# E-0056_STM32.net
KiCad netlist of a schematic drawn in Altium Designer
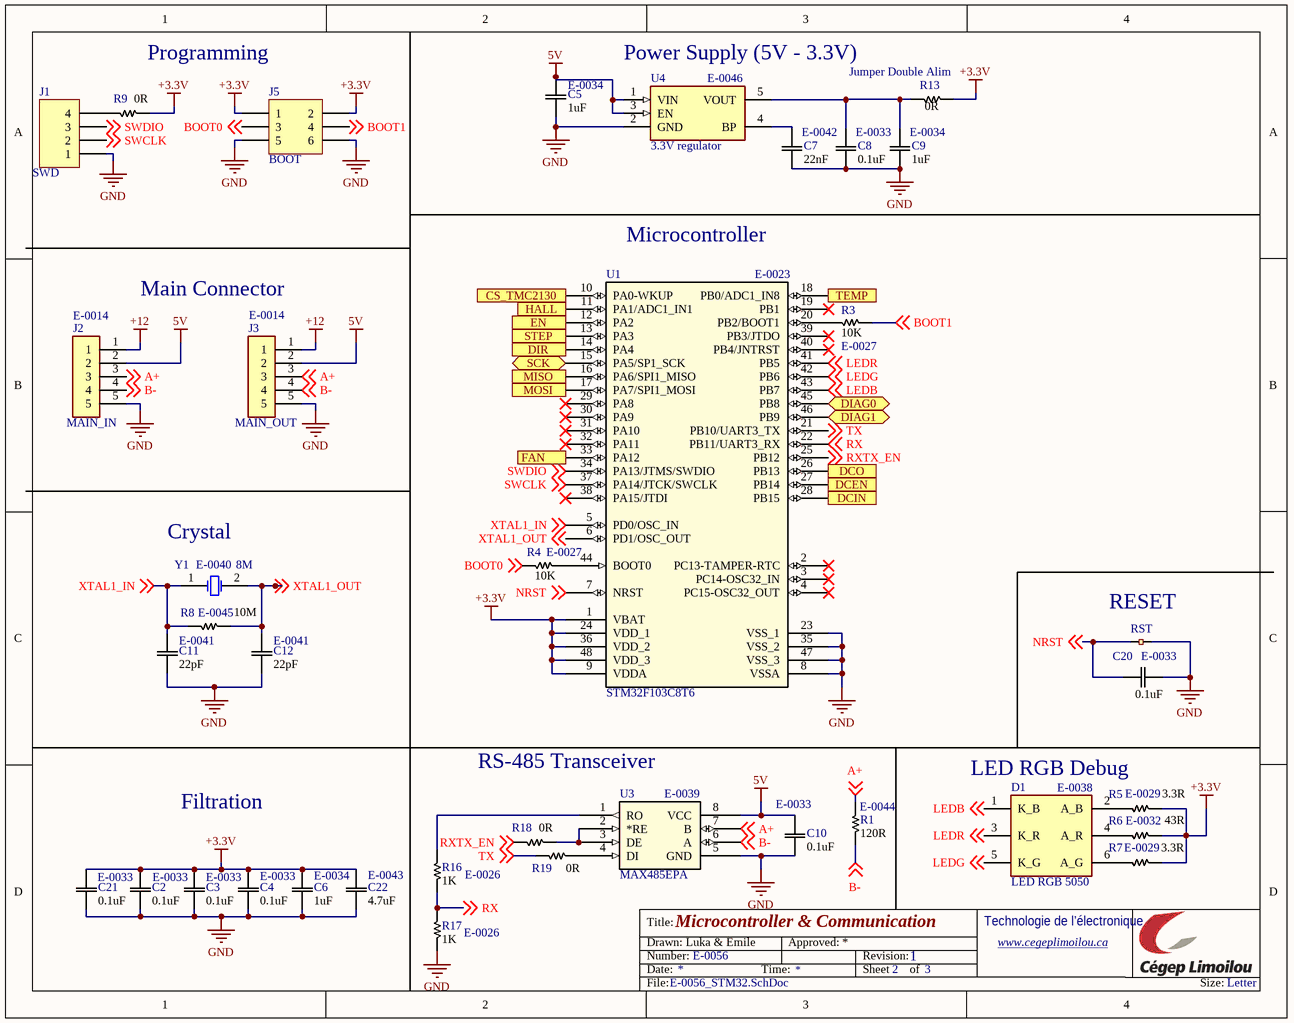
[diagram p0: E-0056_STM32.SchDoc]

(export (version "E")
  (design (tool "Eeschema 10.0.6"))
  (components
    (comp (ref "C2")
      (value "0.1uF")
      (footprint "0603")
      (description "0.1uF Capacitor 0603 SMD")
      (fields
        (field (name "MANUFACTURER_PART_NUMBER") "C0603C104Z3VACTU")
        (field (name "EXCEL NUMBER") "E-0033")
        (field (name "Comment") "E-0033")
        (field (name "COPYRIGHT") "Luka & Émile")
      )
      (libsource (lib "Motor Driver") (part "E-0033"))
    )
    (comp (ref "C3")
      (value "0.1uF")
      (footprint "0603")
      (description "0.1uF Capacitor 0603 SMD")
      (fields
        (field (name "MANUFACTURER_PART_NUMBER") "C0603C104Z3VACTU")
        (field (name "EXCEL NUMBER") "E-0033")
        (field (name "Comment") "E-0033")
        (field (name "COPYRIGHT") "Luka & Émile")
      )
      (libsource (lib "Motor Driver") (part "E-0033"))
    )
    (comp (ref "C4")
      (value "0.1uF")
      (footprint "0603")
      (description "0.1uF Capacitor 0603 SMD")
      (fields
        (field (name "MANUFACTURER_PART_NUMBER") "C0603C104Z3VACTU")
        (field (name "EXCEL NUMBER") "E-0033")
        (field (name "Comment") "E-0033")
        (field (name "COPYRIGHT") "Luka & Émile")
      )
      (libsource (lib "Motor Driver") (part "E-0033"))
    )
    (comp (ref "C5")
      (value "1uF")
      (footprint "0603")
      (description "1uf Capacitor 0603 SMD")
      (fields
        (field (name "MANUFACTURER_PART_NUMBER") "CL10A105KA8NNNC")
        (field (name "EXCEL NUMBER") "E-0034")
        (field (name "Comment") "E-0034")
        (field (name "COPYRIGHT") "Luka & Émile")
      )
      (libsource (lib "Motor Driver") (part "E-0034"))
    )
    (comp (ref "C6")
      (value "1uF")
      (footprint "0603")
      (description "1uf Capacitor 0603 SMD")
      (fields
        (field (name "MANUFACTURER_PART_NUMBER") "CL10A105KA8NNNC")
        (field (name "EXCEL NUMBER") "E-0034")
        (field (name "Comment") "E-0034")
        (field (name "COPYRIGHT") "Luka & Émile")
      )
      (libsource (lib "Motor Driver") (part "E-0034"))
    )
    (comp (ref "C7")
      (value "22nF")
      (footprint "0603")
      (description "22nF Capacitor 0603 SMD")
      (fields
        (field (name "MANUFACTURER_PART_NUMBER") "C0603C223K1RACTU")
        (field (name "EXCEL NUMBER") "E-0042")
        (field (name "Comment") "E-0042")
        (field (name "COPYRIGHT") "Luka & Émile")
      )
      (libsource (lib "Motor Driver") (part "E-0042"))
    )
    (comp (ref "C8")
      (value "0.1uF")
      (footprint "0603")
      (description "0.1uF Capacitor 0603 SMD")
      (fields
        (field (name "MANUFACTURER_PART_NUMBER") "C0603C104Z3VACTU")
        (field (name "EXCEL NUMBER") "E-0033")
        (field (name "Comment") "E-0033")
        (field (name "COPYRIGHT") "Luka & Émile")
      )
      (libsource (lib "Motor Driver") (part "E-0033"))
    )
    (comp (ref "C9")
      (value "1uF")
      (footprint "0603")
      (description "1uf Capacitor 0603 SMD")
      (fields
        (field (name "MANUFACTURER_PART_NUMBER") "CL10A105KA8NNNC")
        (field (name "EXCEL NUMBER") "E-0034")
        (field (name "Comment") "E-0034")
        (field (name "COPYRIGHT") "Luka & Émile")
      )
      (libsource (lib "Motor Driver") (part "E-0034"))
    )
    (comp (ref "C10")
      (value "0.1uF")
      (footprint "0603")
      (description "0.1uF Capacitor 0603 SMD")
      (fields
        (field (name "MANUFACTURER_PART_NUMBER") "C0603C104Z3VACTU")
        (field (name "EXCEL NUMBER") "E-0033")
        (field (name "Comment") "E-0033")
        (field (name "COPYRIGHT") "Luka & Émile")
      )
      (libsource (lib "Motor Driver") (part "E-0033"))
    )
    (comp (ref "C11")
      (value "22pF")
      (footprint "0603")
      (description "22pF Capacitor 0603 SMD")
      (fields
        (field (name "MANUFACTURER_PART_NUMBER") "C0603C220J1GACTU")
        (field (name "EXCEL NUMBER") "E-0041")
        (field (name "Comment") "E-0041")
        (field (name "COPYRIGHT") "Luka & Émile")
      )
      (libsource (lib "Motor Driver") (part "E-0041"))
    )
    (comp (ref "C12")
      (value "22pF")
      (footprint "0603")
      (description "22pF Capacitor 0603 SMD")
      (fields
        (field (name "MANUFACTURER_PART_NUMBER") "C0603C220J1GACTU")
        (field (name "EXCEL NUMBER") "E-0041")
        (field (name "Comment") "E-0041")
        (field (name "COPYRIGHT") "Luka & Émile")
      )
      (libsource (lib "Motor Driver") (part "E-0041"))
    )
    (comp (ref "C20")
      (value "0.1uF")
      (footprint "0603")
      (description "0.1uF Capacitor 0603 SMD")
      (fields
        (field (name "MANUFACTURER_PART_NUMBER") "C0603C104Z3VACTU")
        (field (name "EXCEL NUMBER") "E-0033")
        (field (name "Comment") "E-0033")
        (field (name "COPYRIGHT") "Luka & Émile")
      )
      (libsource (lib "Motor Driver") (part "E-0033"))
    )
    (comp (ref "C21")
      (value "0.1uF")
      (footprint "0603")
      (description "0.1uF Capacitor 0603 SMD")
      (fields
        (field (name "MANUFACTURER_PART_NUMBER") "C0603C104Z3VACTU")
        (field (name "EXCEL NUMBER") "E-0033")
        (field (name "Comment") "E-0033")
        (field (name "COPYRIGHT") "Luka & Émile")
      )
      (libsource (lib "Motor Driver") (part "E-0033"))
    )
    (comp (ref "C22")
      (value "4.7uF")
      (footprint "0603")
      (description "4.7uF Capacitor 0603 SMD")
      (fields
        (field (name "MANUFACTURER_PART_NUMBER") "C0603C475K9PACTU")
        (field (name "EXCEL NUMBER") "E-0043")
        (field (name "Comment") "E-0043")
        (field (name "COPYRIGHT") "Luka & Émile")
      )
      (libsource (lib "Motor Driver") (part "E-0043"))
    )
    (comp (ref "D1")
      (value "LED RGB 5050")
      (footprint "LED 5050")
      (fields
        (field (name "MANUFACTURER_PART_NUMBER") "150505M173300")
        (field (name "EXCEL NUMBER") "E-0038")
        (field (name "COPYRIGHT") "Luka & Émile")
      )
      (libsource (lib "Motor Driver") (part "E-0038"))
    )
    (comp (ref "J1")
      (value "SWD")
      (footprint "HDR1X4")
      (description "Header, 4POS")
      (fields
        (field (name "MANUFACTURER_PART_NUMBER") "61300411121")
        (field (name "COPYRIGHT") "Luka & Émile")
      )
      (libsource (lib "Motor Driver") (part "E-0048"))
    )
    (comp (ref "J2")
      (value "MAIN_IN")
      (footprint "JST 5POS 2.5mm 90°")
      (description "Connector JST 5POS")
      (fields
        (field (name "MANUFACTURER_PART_NUMBER") "S5B-XH-A-1(LF)(SN)")
        (field (name "EXCEL NUMBER") "E-0014")
        (field (name "COPYRIGHT") "Luka & Émile")
      )
      (libsource (lib "Motor Driver") (part "E-0014"))
    )
    (comp (ref "J3")
      (value "MAIN_OUT")
      (footprint "JST 5POS 2.5mm 90°")
      (description "Connector JST 5POS")
      (fields
        (field (name "MANUFACTURER_PART_NUMBER") "S5B-XH-A-1(LF)(SN)")
        (field (name "EXCEL NUMBER") "E-0014")
        (field (name "COPYRIGHT") "Luka & Émile")
      )
      (libsource (lib "Motor Driver") (part "E-0014"))
    )
    (comp (ref "J5")
      (value "BOOT")
      (footprint "Header 3x2 1.27mm SMD")
      (description "Header, 3-Pin, Dual row")
      (fields
        (field (name "MANUFACTURER_PART_NUMBER") "GRPB032VWVN-RC")
        (field (name "COPYRIGHT") "Luka & Émile")
      )
      (libsource (lib "Motor Driver") (part "E-0049"))
    )
    (comp (ref "R1")
      (value "120R")
      (footprint "0603")
      (description "120R Resistor 0603 SMD")
      (fields
        (field (name "MANUFACTURER_PART_NUMBER") "KDV06FR120ET")
        (field (name "EXCEL NUMBER") "E-0044")
        (field (name "Comment") "E-0044")
        (field (name "COPYRIGHT") "Luka & Émile")
      )
      (libsource (lib "Motor Driver") (part "E-0044"))
    )
    (comp (ref "R3")
      (value "10K")
      (footprint "0603")
      (description "10K Resistor 0603 SMD")
      (fields
        (field (name "MANUFACTURER_PART_NUMBER") "RMCF0603JT10K0")
        (field (name "EXCEL NUMBER") "E-0027")
        (field (name "Comment") "Resistor 0603")
        (field (name "COPYRIGHT") "Luka & Émile")
      )
      (libsource (lib "Motor Driver") (part "E-0027"))
    )
    (comp (ref "R4")
      (value "10K")
      (footprint "0603")
      (description "10K Resistor 0603 SMD")
      (fields
        (field (name "MANUFACTURER_PART_NUMBER") "RMCF0603JT10K0")
        (field (name "EXCEL NUMBER") "E-0027")
        (field (name "Comment") "Resistor 0603")
        (field (name "COPYRIGHT") "Luka & Émile")
      )
      (libsource (lib "Motor Driver") (part "E-0027"))
    )
    (comp (ref "R5")
      (value "3.3R")
      (footprint "0603")
      (description "3.3R Resistor 0603 SMD")
      (fields
        (field (name "MANUFACTURER_PART_NUMBER") "MCR03ERTJ3R3")
        (field (name "EXCEL NUMBER") "E-0029")
        (field (name "Comment") "E-0029")
        (field (name "COPYRIGHT") "Luka & Émile")
      )
      (libsource (lib "Motor Driver") (part "E-0029"))
    )
    (comp (ref "R6")
      (value "43R")
      (footprint "0603")
      (description "43R Resistor 0603 SMD")
      (fields
        (field (name "MANUFACTURER_PART_NUMBER") "RK73B1JTTD430J")
        (field (name "EXCEL NUMBER") "E-0032")
        (field (name "Comment") "E-0032")
        (field (name "COPYRIGHT") "Luka & Émile")
      )
      (libsource (lib "Motor Driver") (part "E-0032"))
    )
    (comp (ref "R7")
      (value "3.3R")
      (footprint "0603")
      (description "3.3R Resistor 0603 SMD")
      (fields
        (field (name "MANUFACTURER_PART_NUMBER") "MCR03ERTJ3R3")
        (field (name "EXCEL NUMBER") "E-0029")
        (field (name "Comment") "E-0029")
        (field (name "COPYRIGHT") "Luka & Émile")
      )
      (libsource (lib "Motor Driver") (part "E-0029"))
    )
    (comp (ref "R8")
      (value "10M")
      (footprint "0603")
      (description "10M Resistor 0603 SMD")
      (fields
        (field (name "MANUFACTURER_PART_NUMBER") "CRCW060310M0FKEAC")
        (field (name "EXCEL NUMBER") "E-0045")
        (field (name "Comment") "E-0045")
        (field (name "COPYRIGHT") "Luka & Émile")
      )
      (libsource (lib "Motor Driver") (part "E-0045"))
    )
    (comp (ref "R9")
      (value "0R")
      (footprint "0603")
      (description "Jumper 0603")
      (fields (field (name "Comment") "Jumper") (field (name "COPYRIGHT") "Luka & Émile"))
      (libsource (lib "Motor Driver") (part "Jumper"))
    )
    (comp (ref "R13")
      (value "0R")
      (footprint "0603")
      (description "Jumper 0603")
      (fields (field (name "Comment") "Jumper") (field (name "COPYRIGHT") "Luka & Émile"))
      (libsource (lib "Motor Driver") (part "Jumper"))
    )
    (comp (ref "R16")
      (value "1K")
      (footprint "0603")
      (description "1K Resistor 0603 SMD")
      (fields
        (field (name "MANUFACTURER_PART_NUMBER") "RK73B1JTTD102J")
        (field (name "EXCEL NUMBER") "E-0026")
        (field (name "Comment") "E-0026")
        (field (name "COPYRIGHT") "Luka & Émile")
      )
      (libsource (lib "Motor Driver") (part "E-0026"))
    )
    (comp (ref "R17")
      (value "1K")
      (footprint "0603")
      (description "1K Resistor 0603 SMD")
      (fields
        (field (name "MANUFACTURER_PART_NUMBER") "RK73B1JTTD102J")
        (field (name "EXCEL NUMBER") "E-0026")
        (field (name "Comment") "E-0026")
        (field (name "COPYRIGHT") "Luka & Émile")
      )
      (libsource (lib "Motor Driver") (part "E-0026"))
    )
    (comp (ref "R18")
      (value "0R")
      (footprint "0603")
      (description "Jumper 0603")
      (fields (field (name "Comment") "Jumper") (field (name "COPYRIGHT") "Luka & Émile"))
      (libsource (lib "Motor Driver") (part "Jumper"))
    )
    (comp (ref "R19")
      (value "0R")
      (footprint "0603")
      (description "Jumper 0603")
      (fields (field (name "Comment") "Jumper") (field (name "COPYRIGHT") "Luka & Émile"))
      (libsource (lib "Motor Driver") (part "Jumper"))
    )
    (comp (ref "RST")
      (value "~")
      (footprint "PAD")
      (description "SMD Pad for contact")
      (fields (field (name "COPYRIGHT") "Luka & Émile"))
      (libsource (lib "Motor Driver") (part "PAD"))
    )
    (comp (ref "U1")
      (value "STM32F103C8T6")
      (footprint "LQFP-48")
      (description "STM32F103C8T6 Bluepill")
      (fields
        (field (name "MANUFACTURER_PART_NUMBER") "STM32F103C8T6TR")
        (field (name "EXCEL NUMBER") "E-0023")
        (field (name "COPYRIGHT") "Luka & Émile")
      )
      (libsource (lib "Motor Driver") (part "E-0023"))
    )
    (comp (ref "U3")
      (value "MAX485EPA")
      (footprint "DIP 8 - 3D")
      (description "RS485 Communication")
      (fields
        (field (name "MANUFACTURER_PART_NUMBER") "MAX485CPA+")
        (field (name "EXCEL NUMBER") "E-0039")
        (field (name "COPYRIGHT") "Luka & Émile")
      )
      (libsource (lib "Motor Driver") (part "E-0039"))
    )
    (comp (ref "U4")
      (value "3.3V regulator")
      (footprint "SamacSys:SOT94P279X130-5N")
      (description "Voltage Regulator 3.3V SOT-23-5")
      (fields
        (field (name "MANUFACTURER_PART_NUMBER") "RT9193-28GB")
        (field (name "EXCEL NUMBER") "E-0046")
        (field (name "COPYRIGHT") "Luka & Émile")
      )
      (libsource (lib "Motor Driver") (part "E-0046"))
    )
    (comp (ref "Y1")
      (value "8M")
      (footprint "ATS080B-E")
      (description "Crystal 8M")
      (fields
        (field (name "MANUFACTURER_PART_NUMBER") "ATS080B-E")
        (field (name "EXCEL NUMBER") "E-0040")
        (field (name "COPYRIGHT") "Luka & Émile")
      )
      (libsource (lib "Motor Driver") (part "E-0040"))
    )
  )
  (nets
    (net (code "1") (name "+3.3V") (class "Default")
      (node (ref "C2") (pin "2") (pinfunction "2_2") (pintype "passive"))
      (node (ref "C21") (pin "2") (pinfunction "2_2") (pintype "passive"))
      (node (ref "C22") (pin "2") (pinfunction "2_2") (pintype "passive"))
      (node (ref "C3") (pin "2") (pinfunction "2_2") (pintype "passive"))
      (node (ref "C4") (pin "2") (pinfunction "2_2") (pintype "passive"))
      (node (ref "C6") (pin "2") (pinfunction "2_2") (pintype "passive"))
      (node (ref "J5") (pin "1") (pinfunction "1_1") (pintype "passive"))
      (node (ref "J5") (pin "2") (pinfunction "2_2") (pintype "passive"))
      (node (ref "R13") (pin "2") (pinfunction "2_2") (pintype "passive"))
      (node (ref "R5") (pin "2") (pinfunction "2_2") (pintype "passive"))
      (node (ref "R6") (pin "2") (pinfunction "2_2") (pintype "passive"))
      (node (ref "R7") (pin "2") (pinfunction "2_2") (pintype "passive"))
      (node (ref "R9") (pin "2") (pinfunction "2_2") (pintype "passive"))
      (node (ref "U1") (pin "1") (pinfunction "VBAT_1") (pintype "power_in"))
      (node (ref "U1") (pin "24") (pinfunction "VDD_1_24") (pintype "power_in"))
      (node (ref "U1") (pin "36") (pinfunction "VDD_2_36") (pintype "power_in"))
      (node (ref "U1") (pin "48") (pinfunction "VDD_3_48") (pintype "power_in"))
      (node (ref "U1") (pin "9") (pinfunction "VDDA_9") (pintype "power_in"))
    )
    (net (code "2") (name "+12") (class "Default")
      (node (ref "J2") (pin "1") (pinfunction "1_1") (pintype "passive"))
      (node (ref "J3") (pin "1") (pinfunction "1_1") (pintype "passive"))
    )
    (net (code "3") (name "/CS_TMC2130") (class "Default")
      (node (ref "U1") (pin "10") (pinfunction "PA0-WKUP_10") (pintype "bidirectional"))
    )
    (net (code "4") (name "/DCEN") (class "Default")
      (node (ref "U1") (pin "27") (pinfunction "PB14_27") (pintype "bidirectional"))
    )
    (net (code "5") (name "/DCIN") (class "Default")
      (node (ref "U1") (pin "28") (pinfunction "PB15_28") (pintype "bidirectional"))
    )
    (net (code "6") (name "/DCO") (class "Default")
      (node (ref "U1") (pin "26") (pinfunction "PB13_26") (pintype "bidirectional"))
    )
    (net (code "7") (name "/DIAG0") (class "Default")
      (node (ref "U1") (pin "45") (pinfunction "PB8_45") (pintype "bidirectional"))
    )
    (net (code "8") (name "/DIAG1") (class "Default")
      (node (ref "U1") (pin "46") (pinfunction "PB9_46") (pintype "bidirectional"))
    )
    (net (code "9") (name "/DIR") (class "Default")
      (node (ref "U1") (pin "14") (pinfunction "PA4_14") (pintype "bidirectional"))
    )
    (net (code "10") (name "/EN") (class "Default")
      (node (ref "U1") (pin "12") (pinfunction "PA2_12") (pintype "bidirectional"))
    )
    (net (code "11") (name "/FAN") (class "Default")
      (node (ref "U1") (pin "33") (pinfunction "PA12_33") (pintype "bidirectional"))
    )
    (net (code "12") (name "/HALL") (class "Default")
      (node (ref "U1") (pin "11") (pinfunction "PA1/ADC1_IN1_11") (pintype "bidirectional"))
    )
    (net (code "13") (name "/MISO") (class "Default")
      (node (ref "U1") (pin "16") (pinfunction "PA6/SPI1_MISO_16") (pintype "bidirectional"))
    )
    (net (code "14") (name "/MOSI") (class "Default")
      (node (ref "U1") (pin "17") (pinfunction "PA7/SPI1_MOSI_17") (pintype "bidirectional"))
    )
    (net (code "15") (name "/SCK") (class "Default")
      (node (ref "U1") (pin "15") (pinfunction "PA5/SP1_SCK_15") (pintype "bidirectional"))
    )
    (net (code "16") (name "/STEP") (class "Default")
      (node (ref "U1") (pin "13") (pinfunction "PA3_13") (pintype "bidirectional"))
    )
    (net (code "17") (name "/TEMP") (class "Default")
      (node (ref "U1") (pin "18") (pinfunction "PB0/ADC1_IN8_18") (pintype "bidirectional"))
    )
    (net (code "18") (name "5V") (class "Default")
      (node (ref "C10") (pin "2") (pinfunction "2_2") (pintype "passive"))
      (node (ref "C5") (pin "2") (pinfunction "2_2") (pintype "passive"))
      (node (ref "J2") (pin "2") (pinfunction "2_2") (pintype "passive"))
      (node (ref "J3") (pin "2") (pinfunction "2_2") (pintype "passive"))
      (node (ref "U3") (pin "8") (pinfunction "VCC_8") (pintype "power_in"))
      (node (ref "U4") (pin "1") (pinfunction "VIN_1") (pintype "input"))
      (node (ref "U4") (pin "3") (pinfunction "EN_3") (pintype "input"))
    )
    (net (code "19") (name "A+") (class "Default")
      (node (ref "J2") (pin "3") (pinfunction "3_3") (pintype "passive"))
      (node (ref "J3") (pin "3") (pinfunction "3_3") (pintype "passive"))
      (node (ref "R1") (pin "2") (pinfunction "2_2") (pintype "passive"))
      (node (ref "U3") (pin "7") (pinfunction "B_7") (pintype "bidirectional"))
    )
    (net (code "20") (name "B-") (class "Default")
      (node (ref "J2") (pin "4") (pinfunction "4_4") (pintype "passive"))
      (node (ref "J3") (pin "4") (pinfunction "4_4") (pintype "passive"))
      (node (ref "R1") (pin "1") (pinfunction "1_1") (pintype "passive"))
      (node (ref "U3") (pin "6") (pinfunction "A_6") (pintype "bidirectional"))
    )
    (net (code "21") (name "BOOT0") (class "Default")
      (node (ref "J5") (pin "3") (pinfunction "3_3") (pintype "passive"))
      (node (ref "R4") (pin "1") (pinfunction "1_1") (pintype "passive"))
    )
    (net (code "22") (name "BOOT1") (class "Default")
      (node (ref "J5") (pin "4") (pinfunction "4_4") (pintype "passive"))
      (node (ref "R3") (pin "2") (pinfunction "2_2") (pintype "passive"))
    )
    (net (code "23") (name "GND") (class "Default")
      (node (ref "C10") (pin "1") (pinfunction "1_1") (pintype "passive"))
      (node (ref "C11") (pin "1") (pinfunction "1_1") (pintype "passive"))
      (node (ref "C12") (pin "1") (pinfunction "1_1") (pintype "passive"))
      (node (ref "C2") (pin "1") (pinfunction "1_1") (pintype "passive"))
      (node (ref "C20") (pin "1") (pinfunction "1_1") (pintype "passive"))
      (node (ref "C21") (pin "1") (pinfunction "1_1") (pintype "passive"))
      (node (ref "C22") (pin "1") (pinfunction "1_1") (pintype "passive"))
      (node (ref "C3") (pin "1") (pinfunction "1_1") (pintype "passive"))
      (node (ref "C4") (pin "1") (pinfunction "1_1") (pintype "passive"))
      (node (ref "C5") (pin "1") (pinfunction "1_1") (pintype "passive"))
      (node (ref "C6") (pin "1") (pinfunction "1_1") (pintype "passive"))
      (node (ref "C7") (pin "1") (pinfunction "1_1") (pintype "passive"))
      (node (ref "C8") (pin "1") (pinfunction "1_1") (pintype "passive"))
      (node (ref "C9") (pin "1") (pinfunction "1_1") (pintype "passive"))
      (node (ref "J1") (pin "1") (pinfunction "1_1") (pintype "passive"))
      (node (ref "J2") (pin "5") (pinfunction "5_5") (pintype "passive"))
      (node (ref "J3") (pin "5") (pinfunction "5_5") (pintype "passive"))
      (node (ref "J5") (pin "5") (pinfunction "5_5") (pintype "passive"))
      (node (ref "J5") (pin "6") (pinfunction "6_6") (pintype "passive"))
      (node (ref "R17") (pin "2") (pinfunction "2_2") (pintype "passive"))
      (node (ref "RST") (pin "1") (pinfunction "1_1") (pintype "passive"))
      (node (ref "U1") (pin "23") (pinfunction "VSS_1_23") (pintype "power_in"))
      (node (ref "U1") (pin "35") (pinfunction "VSS_2_35") (pintype "power_in"))
      (node (ref "U1") (pin "47") (pinfunction "VSS_3_47") (pintype "power_in"))
      (node (ref "U1") (pin "8") (pinfunction "VSSA_8") (pintype "power_in"))
      (node (ref "U3") (pin "5") (pinfunction "GND_5") (pintype "power_in"))
      (node (ref "U4") (pin "2") (pinfunction "GND_2") (pintype "power_in"))
    )
    (net (code "24") (name "LEDB") (class "Default")
      (node (ref "D1") (pin "1") (pinfunction "K_B_1") (pintype "passive"))
      (node (ref "U1") (pin "43") (pinfunction "PB7_43") (pintype "bidirectional"))
    )
    (net (code "25") (name "LEDG") (class "Default")
      (node (ref "D1") (pin "5") (pinfunction "K_G_5") (pintype "passive"))
      (node (ref "U1") (pin "42") (pinfunction "PB6_42") (pintype "bidirectional"))
    )
    (net (code "26") (name "LEDR") (class "Default")
      (node (ref "D1") (pin "3") (pinfunction "K_R_3") (pintype "passive"))
      (node (ref "U1") (pin "41") (pinfunction "PB5_41") (pintype "bidirectional"))
    )
    (net (code "27") (name "NRST") (class "Default")
      (node (ref "C20") (pin "2") (pinfunction "2_2") (pintype "passive"))
      (node (ref "RST") (pin "2") (pinfunction "2_2") (pintype "passive"))
      (node (ref "U1") (pin "7") (pinfunction "NRST_7") (pintype "bidirectional"))
    )
    (net (code "28") (name "Net-(D1-A_B)") (class "Default")
      (node (ref "D1") (pin "2") (pinfunction "A_B_2") (pintype "passive"))
      (node (ref "R5") (pin "1") (pinfunction "1_1") (pintype "passive"))
    )
    (net (code "29") (name "Net-(D1-A_G)") (class "Default")
      (node (ref "D1") (pin "6") (pinfunction "A_G_6") (pintype "passive"))
      (node (ref "R7") (pin "1") (pinfunction "1_1") (pintype "passive"))
    )
    (net (code "30") (name "Net-(D1-A_R)") (class "Default")
      (node (ref "D1") (pin "4") (pinfunction "A_R_4") (pintype "passive"))
      (node (ref "R6") (pin "1") (pinfunction "1_1") (pintype "passive"))
    )
    (net (code "31") (name "Net-(J1-Pad4)") (class "Default")
      (node (ref "J1") (pin "4") (pinfunction "4_4") (pintype "passive"))
      (node (ref "R9") (pin "1") (pinfunction "1_1") (pintype "passive"))
    )
    (net (code "32") (name "Net-(U1-BOOT0)") (class "Default")
      (node (ref "R4") (pin "2") (pinfunction "2_2") (pintype "passive"))
      (node (ref "U1") (pin "44") (pinfunction "BOOT0_44") (pintype "input"))
    )
    (net (code "33") (name "Net-(U1-PB2{slash}BOOT1)") (class "Default")
      (node (ref "R3") (pin "1") (pinfunction "1_1") (pintype "passive"))
      (node (ref "U1") (pin "20") (pinfunction "PB2/BOOT1_20") (pintype "bidirectional"))
    )
    (net (code "34") (name "Net-(U3-*RE)") (class "Default")
      (node (ref "R18") (pin "2") (pinfunction "2_2") (pintype "passive"))
      (node (ref "U3") (pin "2") (pinfunction "*RE_2") (pintype "input"))
      (node (ref "U3") (pin "3") (pinfunction "DE_3") (pintype "input"))
    )
    (net (code "35") (name "Net-(U3-DI)") (class "Default")
      (node (ref "R19") (pin "2") (pinfunction "2_2") (pintype "passive"))
      (node (ref "U3") (pin "4") (pinfunction "DI_4") (pintype "input"))
    )
    (net (code "36") (name "Net-(U3-RO)") (class "Default")
      (node (ref "R16") (pin "1") (pinfunction "1_1") (pintype "passive"))
      (node (ref "U3") (pin "1") (pinfunction "RO_1") (pintype "output"))
    )
    (net (code "37") (name "Net-(U4-BP)") (class "Default")
      (node (ref "C7") (pin "2") (pinfunction "2_2") (pintype "passive"))
      (node (ref "U4") (pin "4") (pinfunction "BP_4") (pintype "passive"))
    )
    (net (code "38") (name "Net-(U4-VOUT)") (class "Default")
      (node (ref "C8") (pin "2") (pinfunction "2_2") (pintype "passive"))
      (node (ref "C9") (pin "2") (pinfunction "2_2") (pintype "passive"))
      (node (ref "R13") (pin "1") (pinfunction "1_1") (pintype "passive"))
      (node (ref "U4") (pin "5") (pinfunction "VOUT_5") (pintype "passive"))
    )
    (net (code "39") (name "RX") (class "Default")
      (node (ref "R16") (pin "2") (pinfunction "2_2") (pintype "passive"))
      (node (ref "R17") (pin "1") (pinfunction "1_1") (pintype "passive"))
      (node (ref "U1") (pin "22") (pinfunction "PB11/UART3_RX_22") (pintype "bidirectional"))
    )
    (net (code "40") (name "RXTX_EN") (class "Default")
      (node (ref "R18") (pin "1") (pinfunction "1_1") (pintype "passive"))
      (node (ref "U1") (pin "25") (pinfunction "PB12_25") (pintype "bidirectional"))
    )
    (net (code "41") (name "SWCLK") (class "Default")
      (node (ref "J1") (pin "2") (pinfunction "2_2") (pintype "passive"))
      (node (ref "U1") (pin "37") (pinfunction "PA14/JTCK/SWCLK_37") (pintype "bidirectional"))
    )
    (net (code "42") (name "SWDIO") (class "Default")
      (node (ref "J1") (pin "3") (pinfunction "3_3") (pintype "passive"))
      (node (ref "U1") (pin "34") (pinfunction "PA13/JTMS/SWDIO_34") (pintype "bidirectional"))
    )
    (net (code "43") (name "TX") (class "Default")
      (node (ref "R19") (pin "1") (pinfunction "1_1") (pintype "passive"))
      (node (ref "U1") (pin "21") (pinfunction "PB10/UART3_TX_21") (pintype "bidirectional"))
    )
    (net (code "44") (name "XTAL1_IN") (class "Default")
      (node (ref "C11") (pin "2") (pinfunction "2_2") (pintype "passive"))
      (node (ref "R8") (pin "1") (pinfunction "1_1") (pintype "passive"))
      (node (ref "U1") (pin "5") (pinfunction "PD0/OSC_IN_5") (pintype "bidirectional"))
      (node (ref "Y1") (pin "1") (pinfunction "OSC1_1") (pintype "passive"))
    )
    (net (code "45") (name "XTAL1_OUT") (class "Default")
      (node (ref "C12") (pin "2") (pinfunction "2_2") (pintype "passive"))
      (node (ref "R8") (pin "2") (pinfunction "2_2") (pintype "passive"))
      (node (ref "U1") (pin "6") (pinfunction "PD1/OSC_OUT_6") (pintype "bidirectional"))
      (node (ref "Y1") (pin "2") (pinfunction "OSC2_2") (pintype "passive"))
    )
    (net (code "46") (name "unconnected-(U1-PA8-Pad29)") (class "Default")
      (node (ref "U1") (pin "29") (pinfunction "PA8_29") (pintype "bidirectional+no_connect"))
    )
    (net (code "47") (name "unconnected-(U1-PA9-Pad30)") (class "Default")
      (node (ref "U1") (pin "30") (pinfunction "PA9_30") (pintype "bidirectional+no_connect"))
    )
    (net (code "48") (name "unconnected-(U1-PA10-Pad31)") (class "Default")
      (node (ref "U1") (pin "31") (pinfunction "PA10_31") (pintype "bidirectional+no_connect"))
    )
    (net (code "49") (name "unconnected-(U1-PA11-Pad32)") (class "Default")
      (node (ref "U1") (pin "32") (pinfunction "PA11_32") (pintype "bidirectional+no_connect"))
    )
    (net (code "50") (name "unconnected-(U1-PA15{slash}JTDI-Pad38)") (class "Default")
      (node (ref "U1") (pin "38") (pinfunction "PA15/JTDI_38") (pintype "bidirectional+no_connect"))
    )
    (net (code "51") (name "unconnected-(U1-PB1-Pad19)") (class "Default")
      (node (ref "U1") (pin "19") (pinfunction "PB1_19") (pintype "bidirectional+no_connect"))
    )
    (net (code "52") (name "unconnected-(U1-PB3{slash}JTDO-Pad39)") (class "Default")
      (node (ref "U1") (pin "39") (pinfunction "PB3/JTDO_39") (pintype "bidirectional+no_connect"))
    )
    (net (code "53") (name "unconnected-(U1-PB4{slash}JNTRST-Pad40)") (class "Default")
      (node (ref "U1") (pin "40") (pinfunction "PB4/JNTRST_40") (pintype "bidirectional+no_connect"))
    )
    (net (code "54") (name "unconnected-(U1-PC13-TAMPER-RTC-Pad2)") (class "Default")
      (node (ref "U1") (pin "2") (pinfunction "PC13-TAMPER-RTC_2") (pintype "bidirectional+no_connect"))
    )
    (net (code "55") (name "unconnected-(U1-PC14-OSC32_IN-Pad3)") (class "Default")
      (node (ref "U1") (pin "3") (pinfunction "PC14-OSC32_IN_3") (pintype "bidirectional+no_connect"))
    )
    (net (code "56") (name "unconnected-(U1-PC15-OSC32_OUT-Pad4)") (class "Default")
      (node (ref "U1") (pin "4") (pinfunction "PC15-OSC32_OUT_4") (pintype "bidirectional+no_connect"))
    )
  )
)
